# PSPS_AVNC_SRD_power-2020-10-17.net
KiCad netlist of a schematic drawn in EAGLE
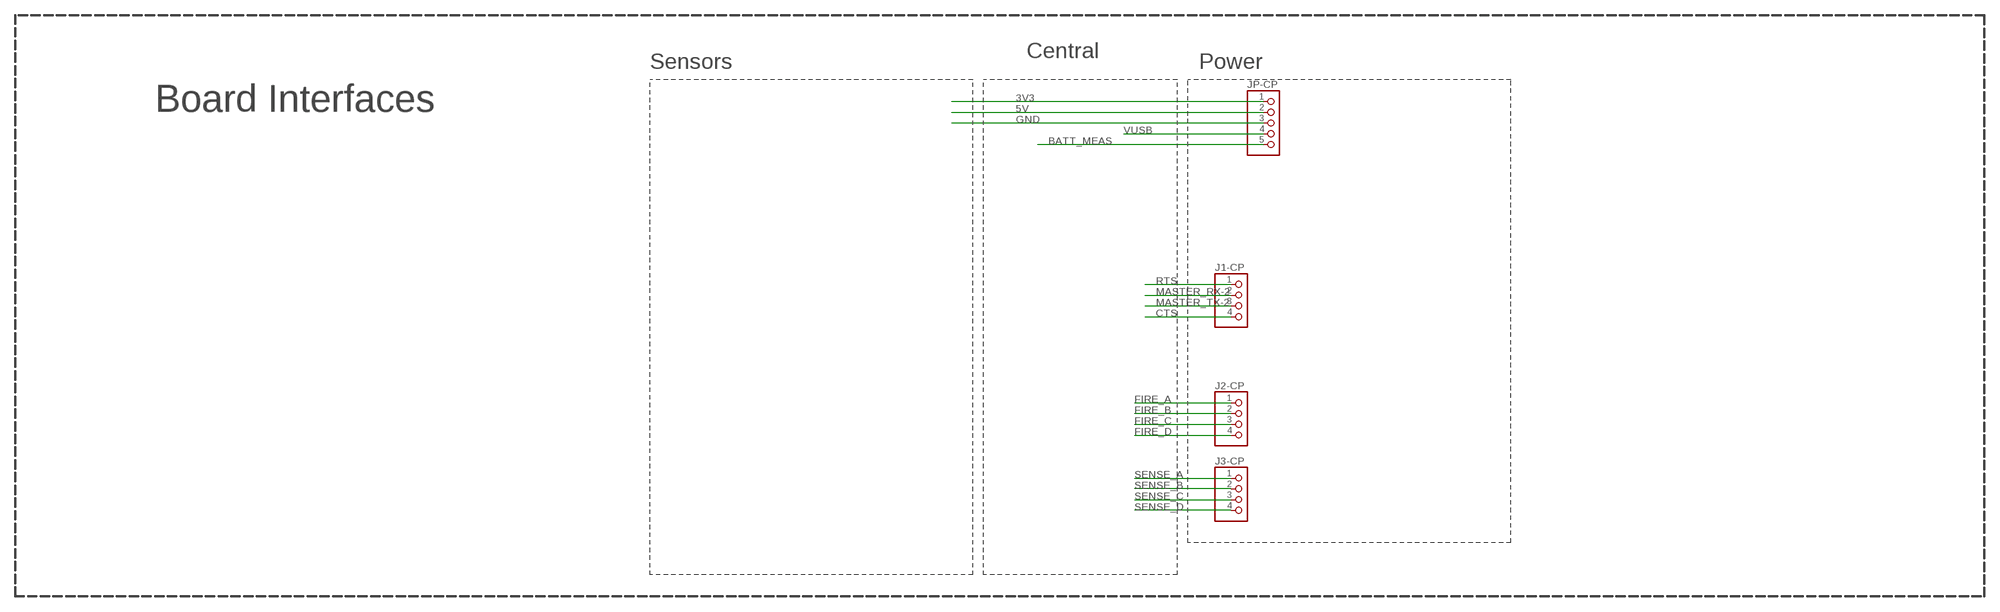
[diagram p0: schematic, sheet 1, part 1 of 3]
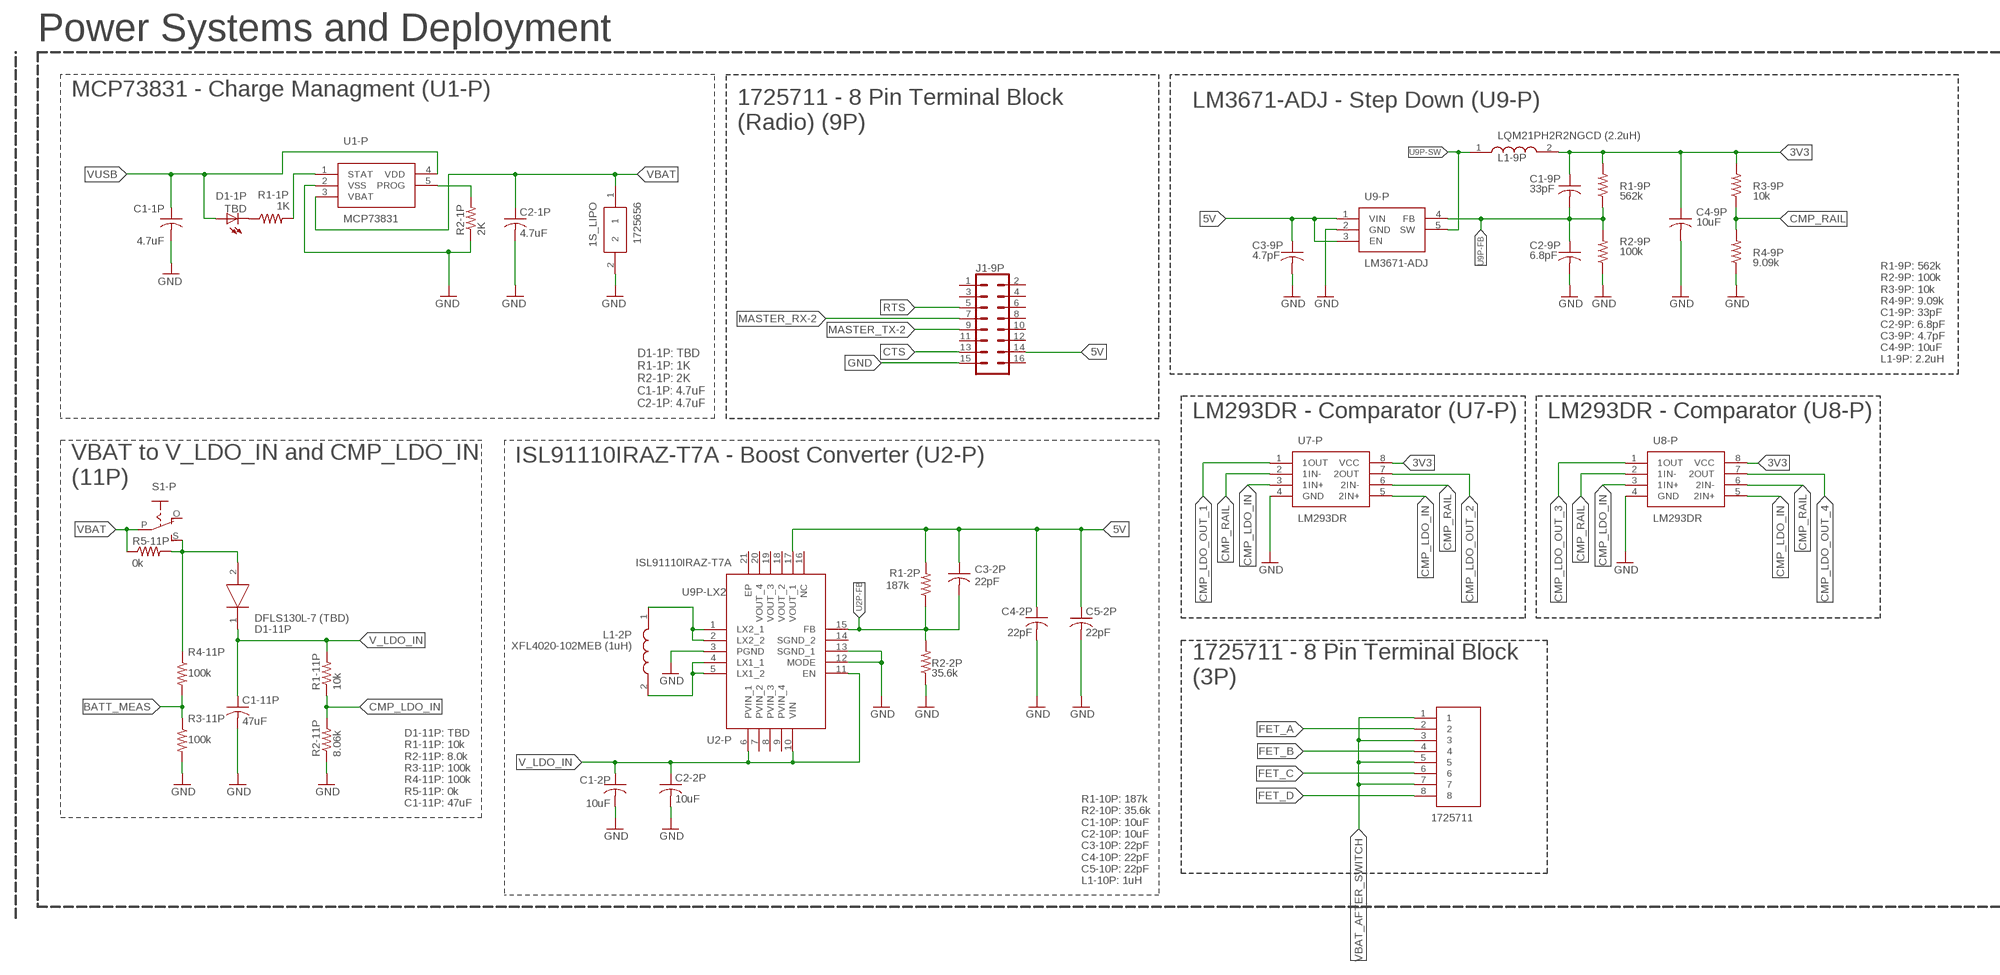
[diagram p1: schematic, sheet 1, part 2 of 3]
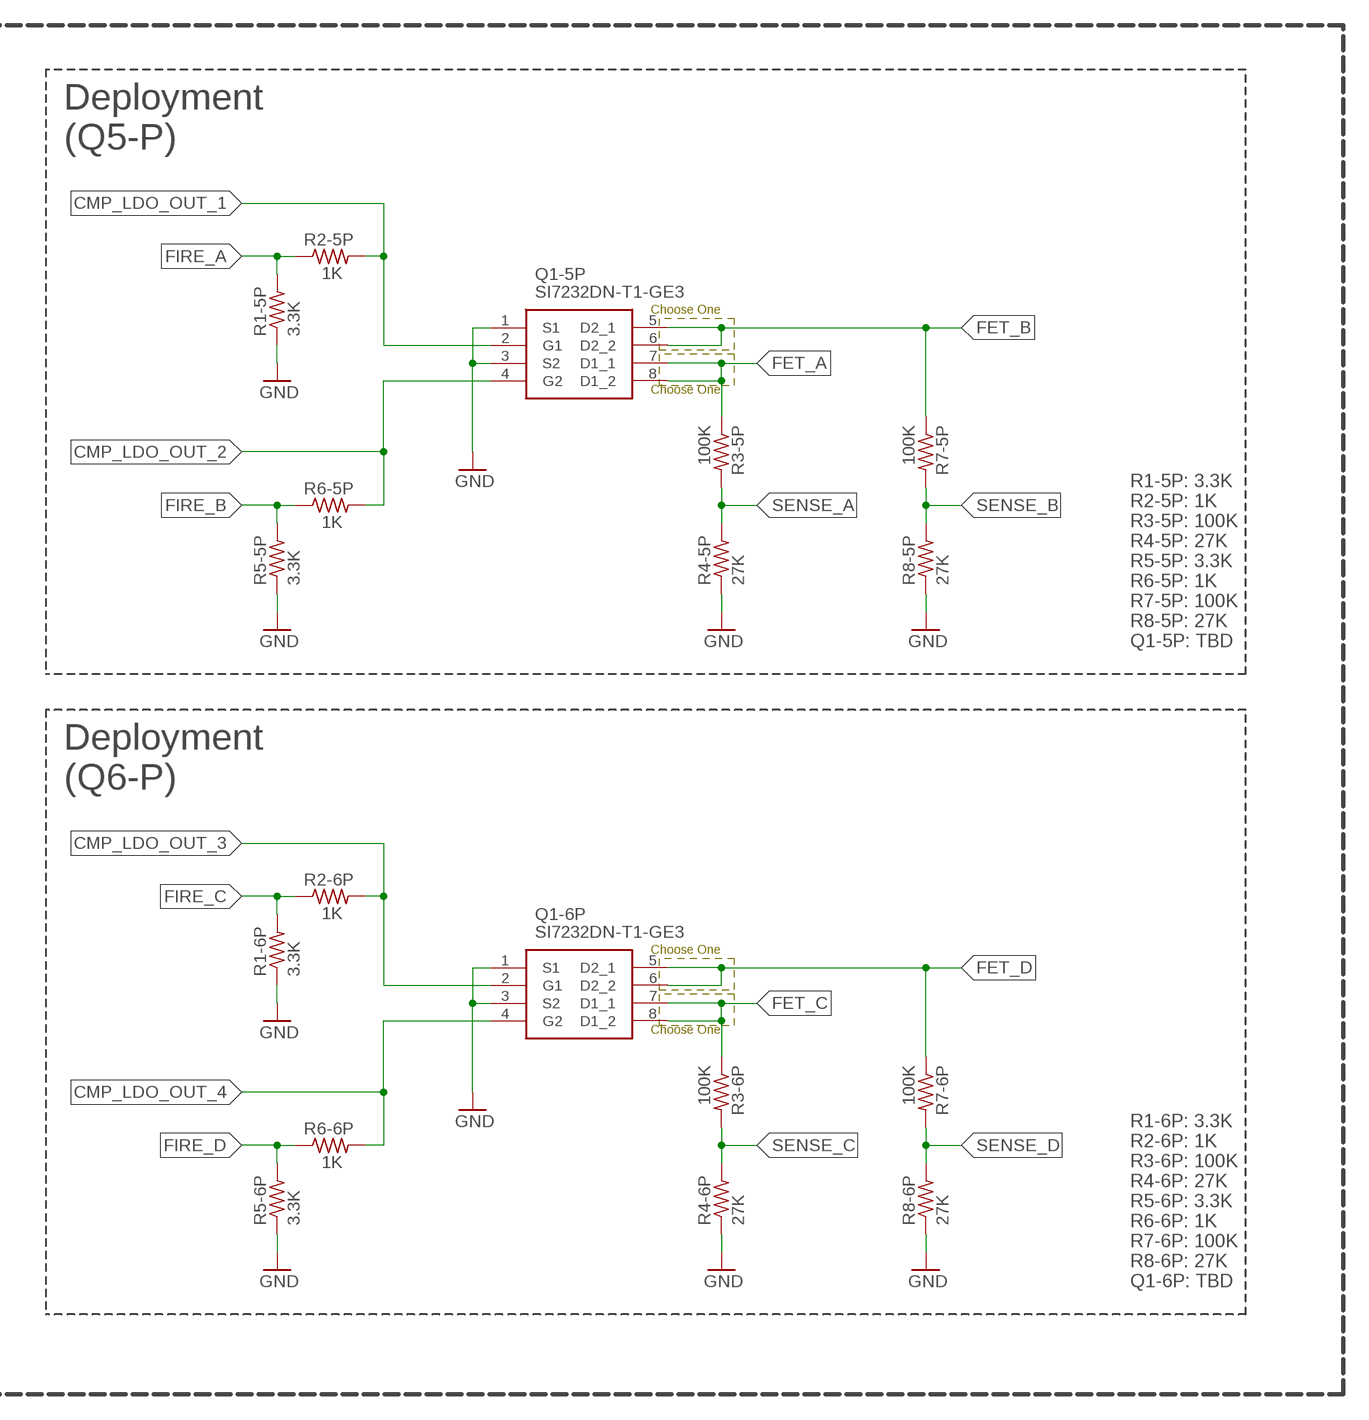
[diagram p2: schematic, sheet 1, part 3 of 3]

(export (version "E")
  (design (tool "Eeschema 10.0.6"))
  (components
    (comp (ref "1S_LIPO")
      (value "1725656")
      (footprint "eagle-import:1725656")
      (fields (field (name "MOUSER_PART_NUMBER") "651-1725656"))
      (libsource (lib "eagle-import") (part "1725656"))
    )
    (comp (ref "C1-1P")
      (value "4.7uF")
      (footprint "eagle-import:C0805")
      (libsource (lib "eagle-import") (part "resistor_348_C-USC0805"))
    )
    (comp (ref "C1-2P")
      (value "10uF")
      (footprint "eagle-import:C0805")
      (libsource (lib "eagle-import") (part "resistor_348_C-USC0805"))
    )
    (comp (ref "C1-9P")
      (value "33pF")
      (footprint "eagle-import:C0805")
      (libsource (lib "eagle-import") (part "resistor_348_C-USC0805"))
    )
    (comp (ref "C1-11P")
      (value "47uF")
      (footprint "eagle-import:C0805")
      (libsource (lib "eagle-import") (part "resistor_348_C-USC0805"))
    )
    (comp (ref "C2-1P")
      (value "4.7uF")
      (footprint "eagle-import:C0805")
      (libsource (lib "eagle-import") (part "resistor_348_C-USC0805"))
    )
    (comp (ref "C2-2P")
      (value "10uF")
      (footprint "eagle-import:C0805")
      (libsource (lib "eagle-import") (part "C-USC0805"))
    )
    (comp (ref "C2-9P")
      (value "6.8pF")
      (footprint "eagle-import:C0805")
      (libsource (lib "eagle-import") (part "resistor_348_C-USC0805"))
    )
    (comp (ref "C3-2P")
      (value "22pF")
      (footprint "eagle-import:C0805")
      (libsource (lib "eagle-import") (part "resistor_348_C-USC0805"))
    )
    (comp (ref "C3-9P")
      (value "4.7pF")
      (footprint "eagle-import:C0805")
      (libsource (lib "eagle-import") (part "resistor_348_C-USC0805"))
    )
    (comp (ref "C4-2P")
      (value "22pF")
      (footprint "eagle-import:C0805")
      (fields (field (name "SPICEPREFIX") "C"))
      (libsource (lib "eagle-import") (part "resistor_348_C-USC0805"))
    )
    (comp (ref "C4-9P")
      (value "10uF")
      (footprint "eagle-import:C0805")
      (libsource (lib "eagle-import") (part "resistor_348_C-USC0805"))
    )
    (comp (ref "C5-2P")
      (value "22pF")
      (footprint "eagle-import:C0805")
      (libsource (lib "eagle-import") (part "C-USC0805"))
    )
    (comp (ref "D1-1P")
      (value "TBD")
      (footprint "eagle-import:CHIPLED_0805")
      (libsource (lib "eagle-import") (part "LEDCHIPLED_0805"))
    )
    (comp (ref "D1-11P")
      (value "DFLS130L-7 (TBD)")
      (footprint "eagle-import:POWERDI_123")
      (fields
        (field (name "MANUFACTURER_PART_NUMBER") "DFLS130L-7")
        (field (name "MOUSER_PART_NUMBER") "621-DFLS130L")
      )
      (libsource (lib "eagle-import") (part "DFLS130L-7"))
    )
    (comp (ref "J1-9P")
      (value "CONN_08X2")
      (footprint "eagle-import:2X8")
      (libsource (lib "eagle-import") (part "CONN_08X2"))
    )
    (comp (ref "J1-CP")
      (value "PINHD-1X4")
      (footprint "eagle-import:1X04")
      (libsource (lib "eagle-import") (part "PINHD-1X4"))
    )
    (comp (ref "J2-CP")
      (value "PINHD-1X4")
      (footprint "eagle-import:1X04")
      (libsource (lib "eagle-import") (part "PINHD-1X4"))
    )
    (comp (ref "J2-P")
      (value "1725711")
      (footprint "eagle-import:1725711")
      (fields (field (name "MOUSER_PART_NUMBER") "651-1725711"))
      (libsource (lib "eagle-import") (part "1725711"))
    )
    (comp (ref "J3-CP")
      (value "PINHD-1X4")
      (footprint "eagle-import:1X04")
      (libsource (lib "eagle-import") (part "PINHD-1X4"))
    )
    (comp (ref "JP-CP")
      (value "PINHD-1X5")
      (footprint "eagle-import:1X05")
      (libsource (lib "eagle-import") (part "PINHD-1X5"))
    )
    (comp (ref "L1-2P")
      (value "XFL4020-102MEB (1uH)")
      (footprint "eagle-import:XFL4020")
      (fields
        (field (name "MANUFACTURER_PART_NUMBER") "XFL4020-102MEB")
        (field (name "MOUSER_PART_NUMBER") "994-XFL4020-102MEB")
      )
      (libsource (lib "eagle-import") (part "XFL4020-102MEB"))
    )
    (comp (ref "L1-9P")
      (value "LQM21PH2R2NGCD (2.2uH)")
      (footprint "eagle-import:INDC2012X100N")
      (fields
        (field (name "MANUFACTURER_PART_NUMBER") "LQM21PH2R2NGCD")
        (field (name "MOUSER_PART_NUMBER") "81-LQM21PH2R2NGCD")
      )
      (libsource (lib "eagle-import") (part "LQM21PH2R2NGCD"))
    )
    (comp (ref "Q1-5P")
      (value "SI7232DN-T1-GE3")
      (footprint "eagle-import:POWERPAK-1212-8")
      (fields (field (name "MOUSER_PART_NUMBER") "781-SI7232DN-GE3"))
      (libsource (lib "eagle-import") (part "SI7232DN-T1-GE3"))
    )
    (comp (ref "Q1-6P")
      (value "SI7232DN-T1-GE3")
      (footprint "eagle-import:POWERPAK-1212-8")
      (fields (field (name "MOUSER_PART_NUMBER") "781-SI7232DN-GE3"))
      (libsource (lib "eagle-import") (part "SI7232DN-T1-GE3"))
    )
    (comp (ref "R1-1P")
      (value "1K")
      (footprint "eagle-import:R0805")
      (libsource (lib "eagle-import") (part "resistor_348_R-US_R0805"))
    )
    (comp (ref "R1-2P")
      (value "187k")
      (footprint "eagle-import:R0805")
      (libsource (lib "eagle-import") (part "resistor_348_R-US_R0805"))
    )
    (comp (ref "R1-5P")
      (value "3.3K")
      (footprint "eagle-import:M0805")
      (libsource (lib "eagle-import") (part "rcl_334_R-US_M0805"))
    )
    (comp (ref "R1-6P")
      (value "3.3K")
      (footprint "eagle-import:M0805")
      (libsource (lib "eagle-import") (part "rcl_334_R-US_M0805"))
    )
    (comp (ref "R1-9P")
      (value "562k")
      (footprint "eagle-import:R0805")
      (libsource (lib "eagle-import") (part "resistor_348_R-US_R0805"))
    )
    (comp (ref "R1-11P")
      (value "10k")
      (footprint "eagle-import:R0805")
      (libsource (lib "eagle-import") (part "resistor_348_R-US_R0805"))
    )
    (comp (ref "R2-1P")
      (value "2K")
      (footprint "eagle-import:R0805")
      (libsource (lib "eagle-import") (part "resistor_348_R-US_R0805"))
    )
    (comp (ref "R2-2P")
      (value "35.6k")
      (footprint "eagle-import:R0805")
      (libsource (lib "eagle-import") (part "resistor_348_R-US_R0805"))
    )
    (comp (ref "R2-5P")
      (value "1K")
      (footprint "eagle-import:M0805")
      (libsource (lib "eagle-import") (part "rcl_334_R-US_M0805"))
    )
    (comp (ref "R2-6P")
      (value "1K")
      (footprint "eagle-import:M0805")
      (libsource (lib "eagle-import") (part "rcl_334_R-US_M0805"))
    )
    (comp (ref "R2-9P")
      (value "100k")
      (footprint "eagle-import:R0805")
      (libsource (lib "eagle-import") (part "resistor_348_R-US_R0805"))
    )
    (comp (ref "R2-11P")
      (value "8.06k")
      (footprint "eagle-import:R0805")
      (libsource (lib "eagle-import") (part "resistor_348_R-US_R0805"))
    )
    (comp (ref "R3-5P")
      (value "100K")
      (footprint "eagle-import:M0805")
      (libsource (lib "eagle-import") (part "rcl_334_R-US_M0805"))
    )
    (comp (ref "R3-6P")
      (value "100K")
      (footprint "eagle-import:M0805")
      (libsource (lib "eagle-import") (part "rcl_334_R-US_M0805"))
    )
    (comp (ref "R3-9P")
      (value "10k")
      (footprint "eagle-import:R0805")
      (libsource (lib "eagle-import") (part "resistor_348_R-US_R0805"))
    )
    (comp (ref "R3-11P")
      (value "100k")
      (footprint "eagle-import:R0805")
      (libsource (lib "eagle-import") (part "R-US_R0805"))
    )
    (comp (ref "R4-5P")
      (value "27K")
      (footprint "eagle-import:M0805")
      (libsource (lib "eagle-import") (part "rcl_334_R-US_M0805"))
    )
    (comp (ref "R4-6P")
      (value "27K")
      (footprint "eagle-import:M0805")
      (libsource (lib "eagle-import") (part "rcl_334_R-US_M0805"))
    )
    (comp (ref "R4-9P")
      (value "9.09k")
      (footprint "eagle-import:R0805")
      (libsource (lib "eagle-import") (part "resistor_348_R-US_R0805"))
    )
    (comp (ref "R4-11P")
      (value "100k")
      (footprint "eagle-import:R0805")
      (libsource (lib "eagle-import") (part "R-US_R0805"))
    )
    (comp (ref "R5-5P")
      (value "3.3K")
      (footprint "eagle-import:M0805")
      (libsource (lib "eagle-import") (part "rcl_334_R-US_M0805"))
    )
    (comp (ref "R5-6P")
      (value "3.3K")
      (footprint "eagle-import:M0805")
      (libsource (lib "eagle-import") (part "rcl_334_R-US_M0805"))
    )
    (comp (ref "R5-11P")
      (value "0k")
      (footprint "eagle-import:R0805")
      (libsource (lib "eagle-import") (part "R-US_R0805"))
    )
    (comp (ref "R6-5P")
      (value "1K")
      (footprint "eagle-import:M0805")
      (libsource (lib "eagle-import") (part "rcl_334_R-US_M0805"))
    )
    (comp (ref "R6-6P")
      (value "1K")
      (footprint "eagle-import:M0805")
      (libsource (lib "eagle-import") (part "rcl_334_R-US_M0805"))
    )
    (comp (ref "R7-5P")
      (value "100K")
      (footprint "eagle-import:M0805")
      (libsource (lib "eagle-import") (part "rcl_334_R-US_M0805"))
    )
    (comp (ref "R7-6P")
      (value "100K")
      (footprint "eagle-import:M0805")
      (libsource (lib "eagle-import") (part "rcl_334_R-US_M0805"))
    )
    (comp (ref "R8-5P")
      (value "27K")
      (footprint "eagle-import:M0805")
      (libsource (lib "eagle-import") (part "rcl_334_R-US_M0805"))
    )
    (comp (ref "R8-6P")
      (value "27K")
      (footprint "eagle-import:M0805")
      (libsource (lib "eagle-import") (part "rcl_334_R-US_M0805"))
    )
    (comp (ref "S1-P")
      (value "EG1218S")
      (footprint "eagle-import:EG1218")
      (libsource (lib "eagle-import") (part "EG1218S"))
    )
    (comp (ref "U1-P")
      (value "MCP73831")
      (footprint "eagle-import:SOT95P270X145-5N")
      (fields
        (field (name "MANUFACTURER_PART_NUMBER") "MCP73831T-2ACI/OT")
        (field (name "MOUSER_PART_NUMBER") "579-MCP73831T-2ACIOT")
      )
      (libsource (lib "eagle-import") (part "MCP73831T-2ACI_OT"))
    )
    (comp (ref "U2-P")
      (value "ISL91110IRAZ-T7A")
      (footprint "eagle-import:QFN50P400X400X100-21N")
      (libsource (lib "eagle-import") (part "ISL91110IRAZ-T7A"))
    )
    (comp (ref "U7-P")
      (value "LM293DR")
      (footprint "eagle-import:SOIC127P600X175-8N")
      (fields (field (name "MOUSER_PART_NUMBER") "595-LM293DR"))
      (libsource (lib "eagle-import") (part "LM293DR"))
    )
    (comp (ref "U8-P")
      (value "LM293DR")
      (footprint "eagle-import:SOIC127P600X175-8N")
      (fields (field (name "MOUSER_PART_NUMBER") "595-LM293DR"))
      (libsource (lib "eagle-import") (part "LM293DR"))
    )
    (comp (ref "U9-P")
      (value "LM3671-ADJ")
      (footprint "eagle-import:SOT95P280X145-5N")
      (fields
        (field (name "MANUFACTURER_PART_NUMBER") "LM3671MFX-ADJ/NOPB")
        (field (name "MOUSER_PART_NUMBER") "926-LM3671MFXADJNOPB")
      )
      (libsource (lib "eagle-import") (part "LM3671MFX-ADJ_NOPB"))
    )
  )
  (nets
    (net (code "1") (name "/U9P-LX2") (class "Default")
      (node (ref "L1-2P") (pin "1") (pinfunction "1_1") (pintype "bidirectional"))
      (node (ref "U2-P") (pin "1") (pinfunction "LX2_1_1") (pintype "bidirectional"))
      (node (ref "U2-P") (pin "2") (pinfunction "LX2_2_2") (pintype "bidirectional"))
    )
    (net (code "2") (name "3V3") (class "Default")
      (node (ref "C1-9P") (pin "1") (pinfunction "1_1") (pintype "passive"))
      (node (ref "C4-9P") (pin "1") (pinfunction "1_1") (pintype "passive"))
      (node (ref "JP-CP") (pin "1") (pinfunction "1_1") (pintype "passive"))
      (node (ref "L1-9P") (pin "2") (pinfunction "2_2") (pintype "bidirectional"))
      (node (ref "R1-9P") (pin "2") (pinfunction "2_2") (pintype "passive"))
      (node (ref "R3-9P") (pin "2") (pinfunction "2_2") (pintype "passive"))
      (node (ref "U7-P") (pin "8") (pinfunction "VCC_8") (pintype "bidirectional"))
      (node (ref "U8-P") (pin "8") (pinfunction "VCC_8") (pintype "bidirectional"))
    )
    (net (code "3") (name "5V") (class "Default")
      (node (ref "C3-2P") (pin "1") (pinfunction "1_1") (pintype "passive"))
      (node (ref "C3-9P") (pin "1") (pinfunction "1_1") (pintype "passive"))
      (node (ref "C4-2P") (pin "1") (pinfunction "1_1") (pintype "passive"))
      (node (ref "C5-2P") (pin "1") (pinfunction "1_1") (pintype "passive"))
      (node (ref "J1-9P") (pin "14") (pinfunction "14_14") (pintype "passive"))
      (node (ref "JP-CP") (pin "2") (pinfunction "2_2") (pintype "passive"))
      (node (ref "R1-2P") (pin "2") (pinfunction "2_2") (pintype "passive"))
      (node (ref "U2-P") (pin "17") (pinfunction "VOUT_1_17") (pintype "bidirectional"))
      (node (ref "U9-P") (pin "1") (pinfunction "VIN_1") (pintype "bidirectional"))
      (node (ref "U9-P") (pin "3") (pinfunction "EN_3") (pintype "bidirectional"))
    )
    (net (code "4") (name "BATT_MEAS") (class "Default")
      (node (ref "JP-CP") (pin "5") (pinfunction "5_5") (pintype "passive"))
      (node (ref "R3-11P") (pin "1") (pinfunction "1_1") (pintype "passive"))
      (node (ref "R4-11P") (pin "2") (pinfunction "2_2") (pintype "passive"))
    )
    (net (code "5") (name "CMP_LDO_IN") (class "Default")
      (node (ref "R1-11P") (pin "1") (pinfunction "1_1") (pintype "passive"))
      (node (ref "R2-11P") (pin "2") (pinfunction "2_2") (pintype "passive"))
      (node (ref "U7-P") (pin "3") (pinfunction "1IN+_3") (pintype "bidirectional"))
      (node (ref "U7-P") (pin "5") (pinfunction "2IN+_5") (pintype "bidirectional"))
      (node (ref "U8-P") (pin "3") (pinfunction "1IN+_3") (pintype "bidirectional"))
      (node (ref "U8-P") (pin "5") (pinfunction "2IN+_5") (pintype "bidirectional"))
    )
    (net (code "6") (name "CMP_LDO_OUT_1") (class "Default")
      (node (ref "Q1-5P") (pin "2") (pinfunction "G1_2") (pintype "bidirectional"))
      (node (ref "R2-5P") (pin "2") (pinfunction "2_2") (pintype "passive"))
      (node (ref "U7-P") (pin "1") (pinfunction "1OUT_1") (pintype "bidirectional"))
    )
    (net (code "7") (name "CMP_LDO_OUT_2") (class "Default")
      (node (ref "Q1-5P") (pin "4") (pinfunction "G2_4") (pintype "bidirectional"))
      (node (ref "R6-5P") (pin "2") (pinfunction "2_2") (pintype "passive"))
      (node (ref "U7-P") (pin "7") (pinfunction "2OUT_7") (pintype "bidirectional"))
    )
    (net (code "8") (name "CMP_LDO_OUT_3") (class "Default")
      (node (ref "Q1-6P") (pin "2") (pinfunction "G1_2") (pintype "bidirectional"))
      (node (ref "R2-6P") (pin "2") (pinfunction "2_2") (pintype "passive"))
      (node (ref "U8-P") (pin "1") (pinfunction "1OUT_1") (pintype "bidirectional"))
    )
    (net (code "9") (name "CMP_LDO_OUT_4") (class "Default")
      (node (ref "Q1-6P") (pin "4") (pinfunction "G2_4") (pintype "bidirectional"))
      (node (ref "R6-6P") (pin "2") (pinfunction "2_2") (pintype "passive"))
      (node (ref "U8-P") (pin "7") (pinfunction "2OUT_7") (pintype "bidirectional"))
    )
    (net (code "10") (name "CMP_RAIL") (class "Default")
      (node (ref "R3-9P") (pin "1") (pinfunction "1_1") (pintype "passive"))
      (node (ref "R4-9P") (pin "2") (pinfunction "2_2") (pintype "passive"))
      (node (ref "U7-P") (pin "2") (pinfunction "1IN-_2") (pintype "bidirectional"))
      (node (ref "U7-P") (pin "6") (pinfunction "2IN-_6") (pintype "bidirectional"))
      (node (ref "U8-P") (pin "2") (pinfunction "1IN-_2") (pintype "bidirectional"))
      (node (ref "U8-P") (pin "6") (pinfunction "2IN-_6") (pintype "bidirectional"))
    )
    (net (code "11") (name "CTS") (class "Default")
      (node (ref "J1-9P") (pin "13") (pinfunction "13_13") (pintype "passive"))
      (node (ref "J1-CP") (pin "4") (pinfunction "4_4") (pintype "passive"))
    )
    (net (code "12") (name "FET_A") (class "Default")
      (node (ref "J2-P") (pin "2") (pinfunction "2_2") (pintype "bidirectional"))
      (node (ref "Q1-5P") (pin "7") (pinfunction "D1_1_7") (pintype "bidirectional"))
      (node (ref "Q1-5P") (pin "8") (pinfunction "D1_2_8") (pintype "bidirectional"))
      (node (ref "R3-5P") (pin "1") (pinfunction "1_1") (pintype "passive"))
    )
    (net (code "13") (name "FET_B") (class "Default")
      (node (ref "J2-P") (pin "4") (pinfunction "4_4") (pintype "bidirectional"))
      (node (ref "Q1-5P") (pin "5") (pinfunction "D2_1_5") (pintype "bidirectional"))
      (node (ref "Q1-5P") (pin "6") (pinfunction "D2_2_6") (pintype "bidirectional"))
      (node (ref "R7-5P") (pin "1") (pinfunction "1_1") (pintype "passive"))
    )
    (net (code "14") (name "FET_C") (class "Default")
      (node (ref "J2-P") (pin "6") (pinfunction "6_6") (pintype "bidirectional"))
      (node (ref "Q1-6P") (pin "7") (pinfunction "D1_1_7") (pintype "bidirectional"))
      (node (ref "Q1-6P") (pin "8") (pinfunction "D1_2_8") (pintype "bidirectional"))
      (node (ref "R3-6P") (pin "1") (pinfunction "1_1") (pintype "passive"))
    )
    (net (code "15") (name "FET_D") (class "Default")
      (node (ref "J2-P") (pin "8") (pinfunction "8_8") (pintype "bidirectional"))
      (node (ref "Q1-6P") (pin "5") (pinfunction "D2_1_5") (pintype "bidirectional"))
      (node (ref "Q1-6P") (pin "6") (pinfunction "D2_2_6") (pintype "bidirectional"))
      (node (ref "R7-6P") (pin "1") (pinfunction "1_1") (pintype "passive"))
    )
    (net (code "16") (name "FIRE_A") (class "Default")
      (node (ref "J2-CP") (pin "1") (pinfunction "1_1") (pintype "passive"))
      (node (ref "R1-5P") (pin "2") (pinfunction "2_2") (pintype "passive"))
      (node (ref "R2-5P") (pin "1") (pinfunction "1_1") (pintype "passive"))
    )
    (net (code "17") (name "FIRE_B") (class "Default")
      (node (ref "J2-CP") (pin "2") (pinfunction "2_2") (pintype "passive"))
      (node (ref "R5-5P") (pin "2") (pinfunction "2_2") (pintype "passive"))
      (node (ref "R6-5P") (pin "1") (pinfunction "1_1") (pintype "passive"))
    )
    (net (code "18") (name "FIRE_C") (class "Default")
      (node (ref "J2-CP") (pin "3") (pinfunction "3_3") (pintype "passive"))
      (node (ref "R1-6P") (pin "2") (pinfunction "2_2") (pintype "passive"))
      (node (ref "R2-6P") (pin "1") (pinfunction "1_1") (pintype "passive"))
    )
    (net (code "19") (name "FIRE_D") (class "Default")
      (node (ref "J2-CP") (pin "4") (pinfunction "4_4") (pintype "passive"))
      (node (ref "R5-6P") (pin "2") (pinfunction "2_2") (pintype "passive"))
      (node (ref "R6-6P") (pin "1") (pinfunction "1_1") (pintype "passive"))
    )
    (net (code "20") (name "GND") (class "Default")
      (node (ref "1S_LIPO") (pin "2") (pinfunction "2_2") (pintype "bidirectional"))
      (node (ref "C1-11P") (pin "2") (pinfunction "2_2") (pintype "passive"))
      (node (ref "C1-1P") (pin "2") (pinfunction "2_2") (pintype "passive"))
      (node (ref "C1-2P") (pin "2") (pinfunction "2_2") (pintype "passive"))
      (node (ref "C2-1P") (pin "2") (pinfunction "2_2") (pintype "passive"))
      (node (ref "C2-2P") (pin "2") (pinfunction "2_2") (pintype "passive"))
      (node (ref "C2-9P") (pin "2") (pinfunction "2_2") (pintype "passive"))
      (node (ref "C3-9P") (pin "2") (pinfunction "2_2") (pintype "passive"))
      (node (ref "C4-2P") (pin "2") (pinfunction "2_2") (pintype "passive"))
      (node (ref "C4-9P") (pin "2") (pinfunction "2_2") (pintype "passive"))
      (node (ref "C5-2P") (pin "2") (pinfunction "2_2") (pintype "passive"))
      (node (ref "J1-9P") (pin "15") (pinfunction "15_15") (pintype "passive"))
      (node (ref "JP-CP") (pin "3") (pinfunction "3_3") (pintype "passive"))
      (node (ref "Q1-5P") (pin "1") (pinfunction "S1_1") (pintype "bidirectional"))
      (node (ref "Q1-5P") (pin "3") (pinfunction "S2_3") (pintype "bidirectional"))
      (node (ref "Q1-6P") (pin "1") (pinfunction "S1_1") (pintype "bidirectional"))
      (node (ref "Q1-6P") (pin "3") (pinfunction "S2_3") (pintype "bidirectional"))
      (node (ref "R1-5P") (pin "1") (pinfunction "1_1") (pintype "passive"))
      (node (ref "R1-6P") (pin "1") (pinfunction "1_1") (pintype "passive"))
      (node (ref "R2-11P") (pin "1") (pinfunction "1_1") (pintype "passive"))
      (node (ref "R2-1P") (pin "1") (pinfunction "1_1") (pintype "passive"))
      (node (ref "R2-2P") (pin "1") (pinfunction "1_1") (pintype "passive"))
      (node (ref "R2-9P") (pin "1") (pinfunction "1_1") (pintype "passive"))
      (node (ref "R3-11P") (pin "2") (pinfunction "2_2") (pintype "passive"))
      (node (ref "R4-5P") (pin "1") (pinfunction "1_1") (pintype "passive"))
      (node (ref "R4-6P") (pin "1") (pinfunction "1_1") (pintype "passive"))
      (node (ref "R4-9P") (pin "1") (pinfunction "1_1") (pintype "passive"))
      (node (ref "R5-5P") (pin "1") (pinfunction "1_1") (pintype "passive"))
      (node (ref "R5-6P") (pin "1") (pinfunction "1_1") (pintype "passive"))
      (node (ref "R8-5P") (pin "1") (pinfunction "1_1") (pintype "passive"))
      (node (ref "R8-6P") (pin "1") (pinfunction "1_1") (pintype "passive"))
      (node (ref "U1-P") (pin "2") (pinfunction "VSS_2") (pintype "bidirectional"))
      (node (ref "U2-P") (pin "12") (pinfunction "MODE_12") (pintype "bidirectional"))
      (node (ref "U2-P") (pin "13") (pinfunction "SGND_1_13") (pintype "bidirectional"))
      (node (ref "U2-P") (pin "3") (pinfunction "PGND_3") (pintype "bidirectional"))
      (node (ref "U7-P") (pin "4") (pinfunction "GND_4") (pintype "bidirectional"))
      (node (ref "U8-P") (pin "4") (pinfunction "GND_4") (pintype "bidirectional"))
      (node (ref "U9-P") (pin "2") (pinfunction "GND_2") (pintype "bidirectional"))
    )
    (net (code "21") (name "MASTER_RX-2") (class "Default")
      (node (ref "J1-9P") (pin "7") (pinfunction "7_7") (pintype "passive"))
      (node (ref "J1-CP") (pin "2") (pinfunction "2_2") (pintype "passive"))
    )
    (net (code "22") (name "MASTER_TX-2") (class "Default")
      (node (ref "J1-9P") (pin "9") (pinfunction "9_9") (pintype "passive"))
      (node (ref "J1-CP") (pin "3") (pinfunction "3_3") (pintype "passive"))
    )
    (net (code "23") (name "Net-(D1-1P-PadC)") (class "Default")
      (node (ref "D1-1P") (pin "C") (pinfunction "C_C") (pintype "passive"))
      (node (ref "R1-1P") (pin "1") (pinfunction "1_1") (pintype "passive"))
    )
    (net (code "24") (name "Net-(U1-P-PROG)") (class "Default")
      (node (ref "R2-1P") (pin "2") (pinfunction "2_2") (pintype "passive"))
      (node (ref "U1-P") (pin "5") (pinfunction "PROG_5") (pintype "bidirectional"))
    )
    (net (code "25") (name "Net-(U1-P-STAT)") (class "Default")
      (node (ref "R1-1P") (pin "2") (pinfunction "2_2") (pintype "passive"))
      (node (ref "U1-P") (pin "1") (pinfunction "STAT_1") (pintype "bidirectional"))
    )
    (net (code "26") (name "Net-(U2-P-LX1_1)") (class "Default")
      (node (ref "L1-2P") (pin "2") (pinfunction "2_2") (pintype "bidirectional"))
      (node (ref "U2-P") (pin "4") (pinfunction "LX1_1_4") (pintype "bidirectional"))
      (node (ref "U2-P") (pin "5") (pinfunction "LX1_2_5") (pintype "bidirectional"))
    )
    (net (code "27") (name "RTS") (class "Default")
      (node (ref "J1-9P") (pin "5") (pinfunction "5_5") (pintype "passive"))
      (node (ref "J1-CP") (pin "1") (pinfunction "1_1") (pintype "passive"))
    )
    (net (code "28") (name "SENSE_A") (class "Default")
      (node (ref "J3-CP") (pin "1") (pinfunction "1_1") (pintype "passive"))
      (node (ref "R3-5P") (pin "2") (pinfunction "2_2") (pintype "passive"))
      (node (ref "R4-5P") (pin "2") (pinfunction "2_2") (pintype "passive"))
    )
    (net (code "29") (name "SENSE_B") (class "Default")
      (node (ref "J3-CP") (pin "2") (pinfunction "2_2") (pintype "passive"))
      (node (ref "R7-5P") (pin "2") (pinfunction "2_2") (pintype "passive"))
      (node (ref "R8-5P") (pin "2") (pinfunction "2_2") (pintype "passive"))
    )
    (net (code "30") (name "SENSE_C") (class "Default")
      (node (ref "J3-CP") (pin "3") (pinfunction "3_3") (pintype "passive"))
      (node (ref "R3-6P") (pin "2") (pinfunction "2_2") (pintype "passive"))
      (node (ref "R4-6P") (pin "2") (pinfunction "2_2") (pintype "passive"))
    )
    (net (code "31") (name "SENSE_D") (class "Default")
      (node (ref "J3-CP") (pin "4") (pinfunction "4_4") (pintype "passive"))
      (node (ref "R7-6P") (pin "2") (pinfunction "2_2") (pintype "passive"))
      (node (ref "R8-6P") (pin "2") (pinfunction "2_2") (pintype "passive"))
    )
    (net (code "32") (name "U2P-FB") (class "Default")
      (node (ref "C3-2P") (pin "2") (pinfunction "2_2") (pintype "passive"))
      (node (ref "R1-2P") (pin "1") (pinfunction "1_1") (pintype "passive"))
      (node (ref "R2-2P") (pin "2") (pinfunction "2_2") (pintype "passive"))
      (node (ref "U2-P") (pin "15") (pinfunction "FB_15") (pintype "bidirectional"))
    )
    (net (code "33") (name "U9P-FB") (class "Default")
      (node (ref "C1-9P") (pin "2") (pinfunction "2_2") (pintype "passive"))
      (node (ref "C2-9P") (pin "1") (pinfunction "1_1") (pintype "passive"))
      (node (ref "R1-9P") (pin "1") (pinfunction "1_1") (pintype "passive"))
      (node (ref "R2-9P") (pin "2") (pinfunction "2_2") (pintype "passive"))
      (node (ref "U9-P") (pin "4") (pinfunction "FB_4") (pintype "bidirectional"))
    )
    (net (code "34") (name "U9P-SW") (class "Default")
      (node (ref "L1-9P") (pin "1") (pinfunction "1_1") (pintype "bidirectional"))
      (node (ref "U9-P") (pin "5") (pinfunction "SW_5") (pintype "bidirectional"))
    )
    (net (code "35") (name "VBAT") (class "Default")
      (node (ref "1S_LIPO") (pin "1") (pinfunction "1_1") (pintype "bidirectional"))
      (node (ref "C2-1P") (pin "1") (pinfunction "1_1") (pintype "passive"))
      (node (ref "R5-11P") (pin "1") (pinfunction "1_1") (pintype "passive"))
      (node (ref "S1-P") (pin "P") (pinfunction "P_P") (pintype "passive"))
      (node (ref "U1-P") (pin "3") (pinfunction "VBAT_3") (pintype "bidirectional"))
    )
    (net (code "36") (name "VBAT_AFTER_SWITCH") (class "Default")
      (node (ref "D1-11P") (pin "2") (pinfunction "A_2") (pintype "bidirectional"))
      (node (ref "J2-P") (pin "1") (pinfunction "1_1") (pintype "bidirectional"))
      (node (ref "J2-P") (pin "3") (pinfunction "3_3") (pintype "bidirectional"))
      (node (ref "J2-P") (pin "5") (pinfunction "5_5") (pintype "bidirectional"))
      (node (ref "J2-P") (pin "7") (pinfunction "7_7") (pintype "bidirectional"))
      (node (ref "R4-11P") (pin "1") (pinfunction "1_1") (pintype "passive"))
      (node (ref "R5-11P") (pin "2") (pinfunction "2_2") (pintype "passive"))
      (node (ref "S1-P") (pin "S") (pinfunction "S_S") (pintype "passive"))
    )
    (net (code "37") (name "VUSB") (class "Default")
      (node (ref "C1-1P") (pin "1") (pinfunction "1_1") (pintype "passive"))
      (node (ref "D1-1P") (pin "A") (pinfunction "A_A") (pintype "passive"))
      (node (ref "JP-CP") (pin "4") (pinfunction "4_4") (pintype "passive"))
      (node (ref "U1-P") (pin "4") (pinfunction "VDD_4") (pintype "bidirectional"))
    )
    (net (code "38") (name "V_LDO_IN") (class "Default")
      (node (ref "C1-11P") (pin "1") (pinfunction "1_1") (pintype "passive"))
      (node (ref "C1-2P") (pin "1") (pinfunction "1_1") (pintype "passive"))
      (node (ref "C2-2P") (pin "1") (pinfunction "1_1") (pintype "passive"))
      (node (ref "D1-11P") (pin "1") (pinfunction "K_1") (pintype "bidirectional"))
      (node (ref "R1-11P") (pin "2") (pinfunction "2_2") (pintype "passive"))
      (node (ref "U2-P") (pin "10") (pinfunction "VIN_10") (pintype "bidirectional"))
      (node (ref "U2-P") (pin "11") (pinfunction "EN_11") (pintype "bidirectional"))
      (node (ref "U2-P") (pin "6") (pinfunction "PVIN_1_6") (pintype "bidirectional"))
    )
    (net (code "39") (name "unconnected-(J1-9P-Pad1)") (class "Default")
      (node (ref "J1-9P") (pin "1") (pinfunction "1_1") (pintype "passive"))
    )
    (net (code "40") (name "unconnected-(J1-9P-Pad2)") (class "Default")
      (node (ref "J1-9P") (pin "2") (pinfunction "2_2") (pintype "passive"))
    )
    (net (code "41") (name "unconnected-(J1-9P-Pad3)") (class "Default")
      (node (ref "J1-9P") (pin "3") (pinfunction "3_3") (pintype "passive"))
    )
    (net (code "42") (name "unconnected-(J1-9P-Pad4)") (class "Default")
      (node (ref "J1-9P") (pin "4") (pinfunction "4_4") (pintype "passive"))
    )
    (net (code "43") (name "unconnected-(J1-9P-Pad6)") (class "Default")
      (node (ref "J1-9P") (pin "6") (pinfunction "6_6") (pintype "passive"))
    )
    (net (code "44") (name "unconnected-(J1-9P-Pad8)") (class "Default")
      (node (ref "J1-9P") (pin "8") (pinfunction "8_8") (pintype "passive"))
    )
    (net (code "45") (name "unconnected-(J1-9P-Pad10)") (class "Default")
      (node (ref "J1-9P") (pin "10") (pinfunction "10_10") (pintype "passive"))
    )
    (net (code "46") (name "unconnected-(J1-9P-Pad11)") (class "Default")
      (node (ref "J1-9P") (pin "11") (pinfunction "11_11") (pintype "passive"))
    )
    (net (code "47") (name "unconnected-(J1-9P-Pad12)") (class "Default")
      (node (ref "J1-9P") (pin "12") (pinfunction "12_12") (pintype "passive"))
    )
    (net (code "48") (name "unconnected-(J1-9P-Pad16)") (class "Default")
      (node (ref "J1-9P") (pin "16") (pinfunction "16_16") (pintype "passive"))
    )
    (net (code "49") (name "unconnected-(S1-P-PadO)") (class "Default")
      (node (ref "S1-P") (pin "O") (pinfunction "O_O") (pintype "passive"))
    )
    (net (code "50") (name "unconnected-(U2-P-EP-Pad21)") (class "Default")
      (node (ref "U2-P") (pin "21") (pinfunction "EP_21") (pintype "bidirectional"))
    )
    (net (code "51") (name "unconnected-(U2-P-NC-Pad16)") (class "Default")
      (node (ref "U2-P") (pin "16") (pinfunction "NC_16") (pintype "no_connect"))
    )
    (net (code "52") (name "unconnected-(U2-P-PVIN_2-Pad7)") (class "Default")
      (node (ref "U2-P") (pin "7") (pinfunction "PVIN_2_7") (pintype "bidirectional"))
    )
    (net (code "53") (name "unconnected-(U2-P-PVIN_3-Pad8)") (class "Default")
      (node (ref "U2-P") (pin "8") (pinfunction "PVIN_3_8") (pintype "bidirectional"))
    )
    (net (code "54") (name "unconnected-(U2-P-PVIN_4-Pad9)") (class "Default")
      (node (ref "U2-P") (pin "9") (pinfunction "PVIN_4_9") (pintype "bidirectional"))
    )
    (net (code "55") (name "unconnected-(U2-P-SGND_2-Pad14)") (class "Default")
      (node (ref "U2-P") (pin "14") (pinfunction "SGND_2_14") (pintype "bidirectional"))
    )
    (net (code "56") (name "unconnected-(U2-P-VOUT_2-Pad18)") (class "Default")
      (node (ref "U2-P") (pin "18") (pinfunction "VOUT_2_18") (pintype "bidirectional"))
    )
    (net (code "57") (name "unconnected-(U2-P-VOUT_3-Pad19)") (class "Default")
      (node (ref "U2-P") (pin "19") (pinfunction "VOUT_3_19") (pintype "bidirectional"))
    )
    (net (code "58") (name "unconnected-(U2-P-VOUT_4-Pad20)") (class "Default")
      (node (ref "U2-P") (pin "20") (pinfunction "VOUT_4_20") (pintype "bidirectional"))
    )
  )
)
